# signal_splitter.net
KiCad netlist of a schematic drawn in EAGLE
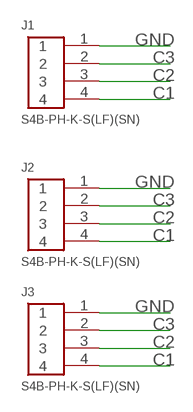
[diagram p0: schematic, sheet 1]

(export (version "E")
  (design (tool "Eeschema 10.0.6"))
  (components
    (comp (ref "J1")
      (value "S4B-PH-K-S(LF)(SN)")
      (footprint "eagle-import:S4B-PH-K-S(LF)(SN)")
      (fields
        (field (name "DIGIKEY_PARTNO") "455-1721-ND")
        (field (name "MANUFACTURER") "JST Sales America Inc.")
        (field (name "CREATED_BY") "PCBLayout.com")
      )
      (libsource (lib "eagle-import") (part "S4B-PH-K-S(LF)(SN)"))
    )
    (comp (ref "J2")
      (value "S4B-PH-K-S(LF)(SN)")
      (footprint "eagle-import:S4B-PH-K-S(LF)(SN)")
      (fields
        (field (name "DIGIKEY_PARTNO") "455-1721-ND")
        (field (name "MANUFACTURER") "JST Sales America Inc.")
        (field (name "CREATED_BY") "PCBLayout.com")
      )
      (libsource (lib "eagle-import") (part "S4B-PH-K-S(LF)(SN)"))
    )
    (comp (ref "J3")
      (value "S4B-PH-K-S(LF)(SN)")
      (footprint "eagle-import:S4B-PH-K-S(LF)(SN)")
      (fields
        (field (name "DIGIKEY_PARTNO") "455-1721-ND")
        (field (name "MANUFACTURER") "JST Sales America Inc.")
        (field (name "CREATED_BY") "PCBLayout.com")
      )
      (libsource (lib "eagle-import") (part "S4B-PH-K-S(LF)(SN)"))
    )
  )
  (nets
    (net (code "1") (name "/C1") (class "Default")
      (node (ref "J1") (pin "4") (pinfunction "4_4") (pintype "passive"))
      (node (ref "J2") (pin "4") (pinfunction "4_4") (pintype "passive"))
      (node (ref "J3") (pin "4") (pinfunction "4_4") (pintype "passive"))
    )
    (net (code "2") (name "/C2") (class "Default")
      (node (ref "J1") (pin "3") (pinfunction "3_3") (pintype "passive"))
      (node (ref "J2") (pin "3") (pinfunction "3_3") (pintype "passive"))
      (node (ref "J3") (pin "3") (pinfunction "3_3") (pintype "passive"))
    )
    (net (code "3") (name "/C3") (class "Default")
      (node (ref "J1") (pin "2") (pinfunction "2_2") (pintype "passive"))
      (node (ref "J2") (pin "2") (pinfunction "2_2") (pintype "passive"))
      (node (ref "J3") (pin "2") (pinfunction "2_2") (pintype "passive"))
    )
    (net (code "4") (name "/GND") (class "Default")
      (node (ref "J1") (pin "1") (pinfunction "1_1") (pintype "passive"))
      (node (ref "J2") (pin "1") (pinfunction "1_1") (pintype "passive"))
      (node (ref "J3") (pin "1") (pinfunction "1_1") (pintype "passive"))
    )
  )
)
